# amp_tda2030_2ch_ocl.net
KiCad netlist of a schematic drawn in EAGLE
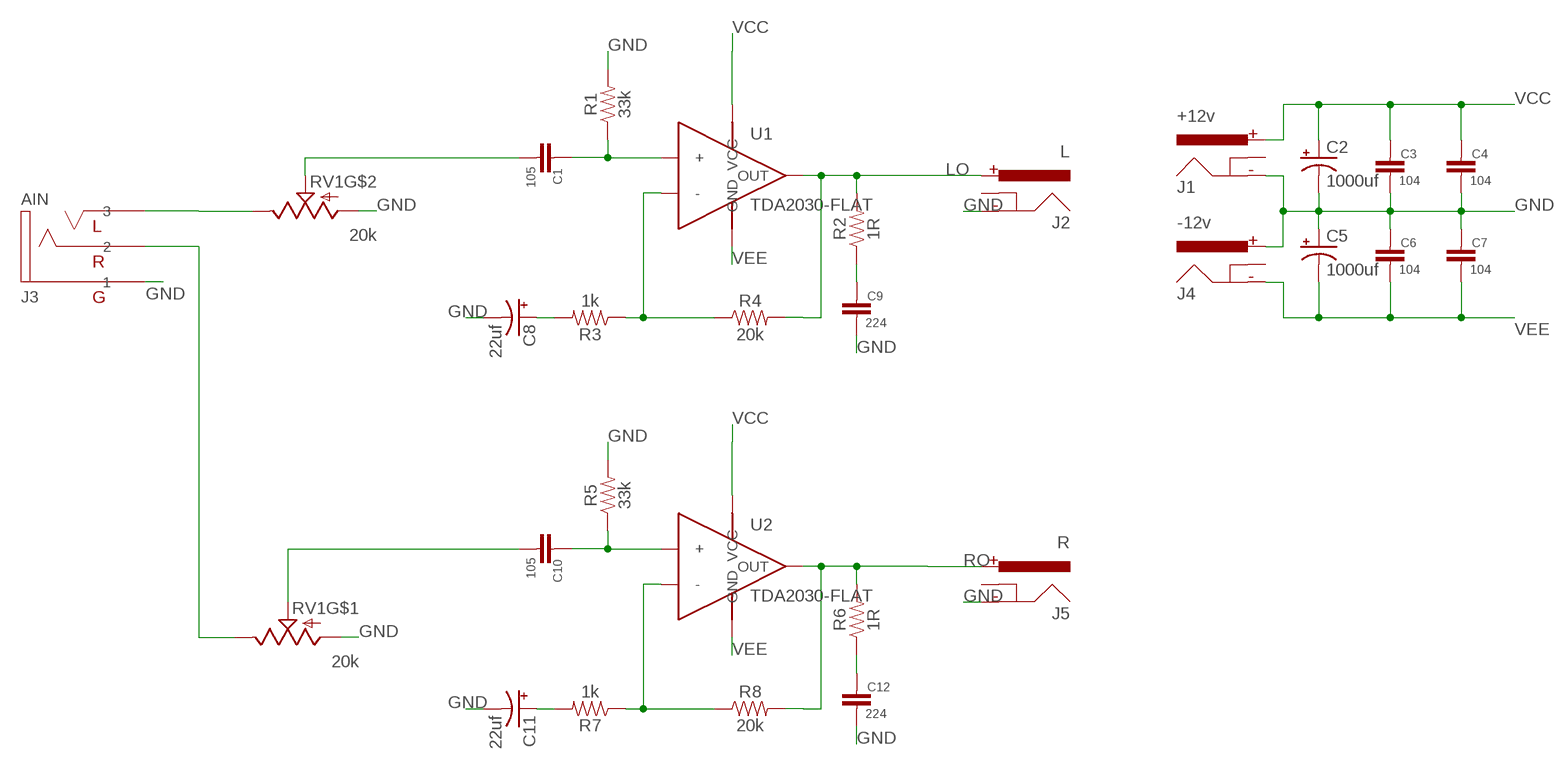
[diagram p0: schematic, sheet 1]

(export (version "E")
  (design (tool "Eeschema 10.0.6"))
  (components
    (comp (ref "C1")
      (value "105")
      (footprint "eagle-import:CAP_5MM")
      (libsource (lib "eagle-import") (part "CAP_P"))
    )
    (comp (ref "C2")
      (value "1000uf")
      (footprint "eagle-import:CAP_5MM_10D")
      (libsource (lib "eagle-import") (part "CAP5MM"))
    )
    (comp (ref "C3")
      (value "104")
      (footprint "eagle-import:C0603")
      (libsource (lib "eagle-import") (part "CAP_SMDC0603"))
    )
    (comp (ref "C4")
      (value "104")
      (footprint "eagle-import:C0603")
      (libsource (lib "eagle-import") (part "CAP_SMDC0603"))
    )
    (comp (ref "C5")
      (value "1000uf")
      (footprint "eagle-import:CAP_5MM_10D")
      (libsource (lib "eagle-import") (part "CAP5MM"))
    )
    (comp (ref "C6")
      (value "104")
      (footprint "eagle-import:C0603")
      (libsource (lib "eagle-import") (part "CAP_SMDC0603"))
    )
    (comp (ref "C7")
      (value "104")
      (footprint "eagle-import:C0603")
      (libsource (lib "eagle-import") (part "CAP_SMDC0603"))
    )
    (comp (ref "C8")
      (value "22uf")
      (footprint "eagle-import:CAP_2.5MM")
      (libsource (lib "eagle-import") (part "CAP"))
    )
    (comp (ref "C9")
      (value "224")
      (footprint "eagle-import:C0603")
      (libsource (lib "eagle-import") (part "CAP_SMDC0603"))
    )
    (comp (ref "C10")
      (value "105")
      (footprint "eagle-import:CAP_5MM")
      (libsource (lib "eagle-import") (part "CAP_P"))
    )
    (comp (ref "C11")
      (value "22uf")
      (footprint "eagle-import:CAP_2.5MM")
      (libsource (lib "eagle-import") (part "CAP"))
    )
    (comp (ref "C12")
      (value "224")
      (footprint "eagle-import:C0603")
      (libsource (lib "eagle-import") (part "CAP_SMDC0603"))
    )
    (comp (ref "J1")
      (value "+12v")
      (footprint "eagle-import:POWER_JACK_PTH_LOCK")
      (libsource (lib "eagle-import") (part "POWER_JACKPTH_LOCK"))
    )
    (comp (ref "J2")
      (value "L")
      (footprint "eagle-import:POWER_JACK_PTH_LOCK")
      (libsource (lib "eagle-import") (part "POWER_JACKPTH_LOCK"))
    )
    (comp (ref "J3")
      (value "AIN")
      (footprint "eagle-import:3.5MM")
      (libsource (lib "eagle-import") (part "3.5MM_PHONE"))
    )
    (comp (ref "J4")
      (value "-12v")
      (footprint "eagle-import:POWER_JACK_PTH_LOCK")
      (libsource (lib "eagle-import") (part "POWER_JACKPTH_LOCK"))
    )
    (comp (ref "J5")
      (value "R")
      (footprint "eagle-import:POWER_JACK_PTH_LOCK")
      (libsource (lib "eagle-import") (part "POWER_JACKPTH_LOCK"))
    )
    (comp (ref "R1")
      (value "33k")
      (footprint "eagle-import:R0603")
      (libsource (lib "eagle-import") (part "RESISTOR_SMDR0603"))
    )
    (comp (ref "R2")
      (value "1R")
      (footprint "eagle-import:R0603")
      (libsource (lib "eagle-import") (part "RESISTOR_SMDR0603"))
    )
    (comp (ref "R3")
      (value "1k")
      (footprint "eagle-import:R0603")
      (libsource (lib "eagle-import") (part "RESISTOR_SMDR0603"))
    )
    (comp (ref "R4")
      (value "20k")
      (footprint "eagle-import:R0603")
      (libsource (lib "eagle-import") (part "RESISTOR_SMDR0603"))
    )
    (comp (ref "R5")
      (value "33k")
      (footprint "eagle-import:R0603")
      (libsource (lib "eagle-import") (part "RESISTOR_SMDR0603"))
    )
    (comp (ref "R6")
      (value "1R")
      (footprint "eagle-import:R0603")
      (libsource (lib "eagle-import") (part "RESISTOR_SMDR0603"))
    )
    (comp (ref "R7")
      (value "1k")
      (footprint "eagle-import:R0603")
      (libsource (lib "eagle-import") (part "RESISTOR_SMDR0603"))
    )
    (comp (ref "R8")
      (value "20k")
      (footprint "eagle-import:R0603")
      (libsource (lib "eagle-import") (part "RESISTOR_SMDR0603"))
    )
    (comp (ref "RV1")
      (value "20k")
      (footprint "eagle-import:POT_DUAL_GREEN")
      (libsource (lib "eagle-import") (part "POT_DUALPOT_DUAL_GREEN"))
    )
    (comp (ref "U1")
      (value "TDA2030-FLAT")
      (footprint "eagle-import:TO220-FLAT")
      (libsource (lib "eagle-import") (part "TDA2030-FLAT"))
    )
    (comp (ref "U2")
      (value "TDA2030-FLAT")
      (footprint "eagle-import:TO220-FLAT")
      (libsource (lib "eagle-import") (part "TDA2030-FLAT"))
    )
  )
  (nets
    (net (code "1") (name "/GND") (class "Default")
      (node (ref "C11") (pin "-") (pinfunction "-_-") (pintype "passive"))
      (node (ref "C12") (pin "2") (pinfunction "2_2") (pintype "passive"))
      (node (ref "C2") (pin "-") (pinfunction "-_-") (pintype "passive"))
      (node (ref "C3") (pin "2") (pinfunction "2_2") (pintype "passive"))
      (node (ref "C4") (pin "2") (pinfunction "2_2") (pintype "passive"))
      (node (ref "C5") (pin "+") (pinfunction "+_+") (pintype "passive"))
      (node (ref "C6") (pin "1") (pinfunction "1_1") (pintype "passive"))
      (node (ref "C7") (pin "1") (pinfunction "1_1") (pintype "passive"))
      (node (ref "C8") (pin "-") (pinfunction "-_-") (pintype "passive"))
      (node (ref "C9") (pin "2") (pinfunction "2_2") (pintype "passive"))
      (node (ref "J1") (pin "GND") (pinfunction "GND_GND") (pintype "bidirectional"))
      (node (ref "J2") (pin "GND") (pinfunction "GND_GND") (pintype "bidirectional"))
      (node (ref "J3") (pin "P$1") (pinfunction "1_P$1") (pintype "bidirectional"))
      (node (ref "J4") (pin "PWR") (pinfunction "PWR_PWR") (pintype "bidirectional"))
      (node (ref "J5") (pin "GND") (pinfunction "GND_GND") (pintype "bidirectional"))
      (node (ref "R1") (pin "2") (pinfunction "2_2") (pintype "passive"))
      (node (ref "R5") (pin "2") (pinfunction "2_2") (pintype "passive"))
      (node (ref "RV1") (pin "P$1") (pinfunction "A_P$1") (pintype "passive"))
      (node (ref "RV1") (pin "P$4") (pinfunction "A_P$4") (pintype "passive"))
    )
    (net (code "2") (name "/LO") (class "Default")
      (node (ref "J2") (pin "PWR") (pinfunction "PWR_PWR") (pintype "bidirectional"))
      (node (ref "R2") (pin "2") (pinfunction "2_2") (pintype "passive"))
      (node (ref "R4") (pin "2") (pinfunction "2_2") (pintype "passive"))
      (node (ref "U1") (pin "4") (pinfunction "OUT_4") (pintype "bidirectional"))
    )
    (net (code "3") (name "/RO") (class "Default")
      (node (ref "J5") (pin "PWR") (pinfunction "PWR_PWR") (pintype "bidirectional"))
      (node (ref "R6") (pin "2") (pinfunction "2_2") (pintype "passive"))
      (node (ref "R8") (pin "2") (pinfunction "2_2") (pintype "passive"))
      (node (ref "U2") (pin "4") (pinfunction "OUT_4") (pintype "bidirectional"))
    )
    (net (code "4") (name "/VCC") (class "Default")
      (node (ref "C2") (pin "+") (pinfunction "+_+") (pintype "passive"))
      (node (ref "C3") (pin "1") (pinfunction "1_1") (pintype "passive"))
      (node (ref "C4") (pin "1") (pinfunction "1_1") (pintype "passive"))
      (node (ref "J1") (pin "PWR") (pinfunction "PWR_PWR") (pintype "bidirectional"))
      (node (ref "U1") (pin "5") (pinfunction "VCC_5") (pintype "bidirectional"))
      (node (ref "U2") (pin "5") (pinfunction "VCC_5") (pintype "bidirectional"))
    )
    (net (code "5") (name "/VEE") (class "Default")
      (node (ref "C5") (pin "-") (pinfunction "-_-") (pintype "passive"))
      (node (ref "C6") (pin "2") (pinfunction "2_2") (pintype "passive"))
      (node (ref "C7") (pin "2") (pinfunction "2_2") (pintype "passive"))
      (node (ref "J4") (pin "GND") (pinfunction "GND_GND") (pintype "bidirectional"))
      (node (ref "U1") (pin "3") (pinfunction "GND_3") (pintype "bidirectional"))
      (node (ref "U1") (pin "TAB") (pinfunction "GND_TAB") (pintype "bidirectional"))
      (node (ref "U2") (pin "3") (pinfunction "GND_3") (pintype "bidirectional"))
      (node (ref "U2") (pin "TAB") (pinfunction "GND_TAB") (pintype "bidirectional"))
    )
    (net (code "6") (name "Net-(C1-1)") (class "Default")
      (node (ref "C1") (pin "P$1") (pinfunction "1_P$1") (pintype "passive"))
      (node (ref "R1") (pin "1") (pinfunction "1_1") (pintype "passive"))
      (node (ref "U1") (pin "1") (pinfunction "+_1") (pintype "bidirectional"))
    )
    (net (code "7") (name "Net-(C1-2)") (class "Default")
      (node (ref "C1") (pin "P$2") (pinfunction "2_P$2") (pintype "passive"))
      (node (ref "RV1") (pin "P$5") (pinfunction "S_P$5") (pintype "passive"))
    )
    (net (code "8") (name "Net-(C8-Pad+)") (class "Default")
      (node (ref "C8") (pin "+") (pinfunction "+_+") (pintype "passive"))
      (node (ref "R3") (pin "2") (pinfunction "2_2") (pintype "passive"))
    )
    (net (code "9") (name "Net-(C9-Pad1)") (class "Default")
      (node (ref "C9") (pin "1") (pinfunction "1_1") (pintype "passive"))
      (node (ref "R2") (pin "1") (pinfunction "1_1") (pintype "passive"))
    )
    (net (code "10") (name "Net-(C10-1)") (class "Default")
      (node (ref "C10") (pin "P$1") (pinfunction "1_P$1") (pintype "passive"))
      (node (ref "R5") (pin "1") (pinfunction "1_1") (pintype "passive"))
      (node (ref "U2") (pin "1") (pinfunction "+_1") (pintype "bidirectional"))
    )
    (net (code "11") (name "Net-(C10-2)") (class "Default")
      (node (ref "C10") (pin "P$2") (pinfunction "2_P$2") (pintype "passive"))
      (node (ref "RV1") (pin "P$2") (pinfunction "S_P$2") (pintype "passive"))
    )
    (net (code "12") (name "Net-(C11-Pad+)") (class "Default")
      (node (ref "C11") (pin "+") (pinfunction "+_+") (pintype "passive"))
      (node (ref "R7") (pin "2") (pinfunction "2_2") (pintype "passive"))
    )
    (net (code "13") (name "Net-(C12-Pad1)") (class "Default")
      (node (ref "C12") (pin "1") (pinfunction "1_1") (pintype "passive"))
      (node (ref "R6") (pin "1") (pinfunction "1_1") (pintype "passive"))
    )
    (net (code "14") (name "Net-(J3-2)") (class "Default")
      (node (ref "J3") (pin "P$2") (pinfunction "2_P$2") (pintype "bidirectional"))
      (node (ref "RV1") (pin "P$3") (pinfunction "E_P$3") (pintype "passive"))
    )
    (net (code "15") (name "Net-(J3-3)") (class "Default")
      (node (ref "J3") (pin "P$3") (pinfunction "3_P$3") (pintype "bidirectional"))
      (node (ref "RV1") (pin "P$6") (pinfunction "E_P$6") (pintype "passive"))
    )
    (net (code "16") (name "Net-(U1--)") (class "Default")
      (node (ref "R3") (pin "1") (pinfunction "1_1") (pintype "passive"))
      (node (ref "R4") (pin "1") (pinfunction "1_1") (pintype "passive"))
      (node (ref "U1") (pin "2") (pinfunction "-_2") (pintype "bidirectional"))
    )
    (net (code "17") (name "Net-(U2--)") (class "Default")
      (node (ref "R7") (pin "1") (pinfunction "1_1") (pintype "passive"))
      (node (ref "R8") (pin "1") (pinfunction "1_1") (pintype "passive"))
      (node (ref "U2") (pin "2") (pinfunction "-_2") (pintype "bidirectional"))
    )
    (net (code "18") (name "unconnected-(J1-PadGNDBREAK)") (class "Default")
      (node (ref "J1") (pin "GNDBREAK") (pinfunction "GNDBREAK_GNDBREAK") (pintype "bidirectional"))
    )
    (net (code "19") (name "unconnected-(J2-PadGNDBREAK)") (class "Default")
      (node (ref "J2") (pin "GNDBREAK") (pinfunction "GNDBREAK_GNDBREAK") (pintype "bidirectional"))
    )
    (net (code "20") (name "unconnected-(J4-PadGNDBREAK)") (class "Default")
      (node (ref "J4") (pin "GNDBREAK") (pinfunction "GNDBREAK_GNDBREAK") (pintype "bidirectional"))
    )
    (net (code "21") (name "unconnected-(J5-PadGNDBREAK)") (class "Default")
      (node (ref "J5") (pin "GNDBREAK") (pinfunction "GNDBREAK_GNDBREAK") (pintype "bidirectional"))
    )
  )
)
